# stm32070.net
KiCad netlist of a schematic drawn in Altium Designer
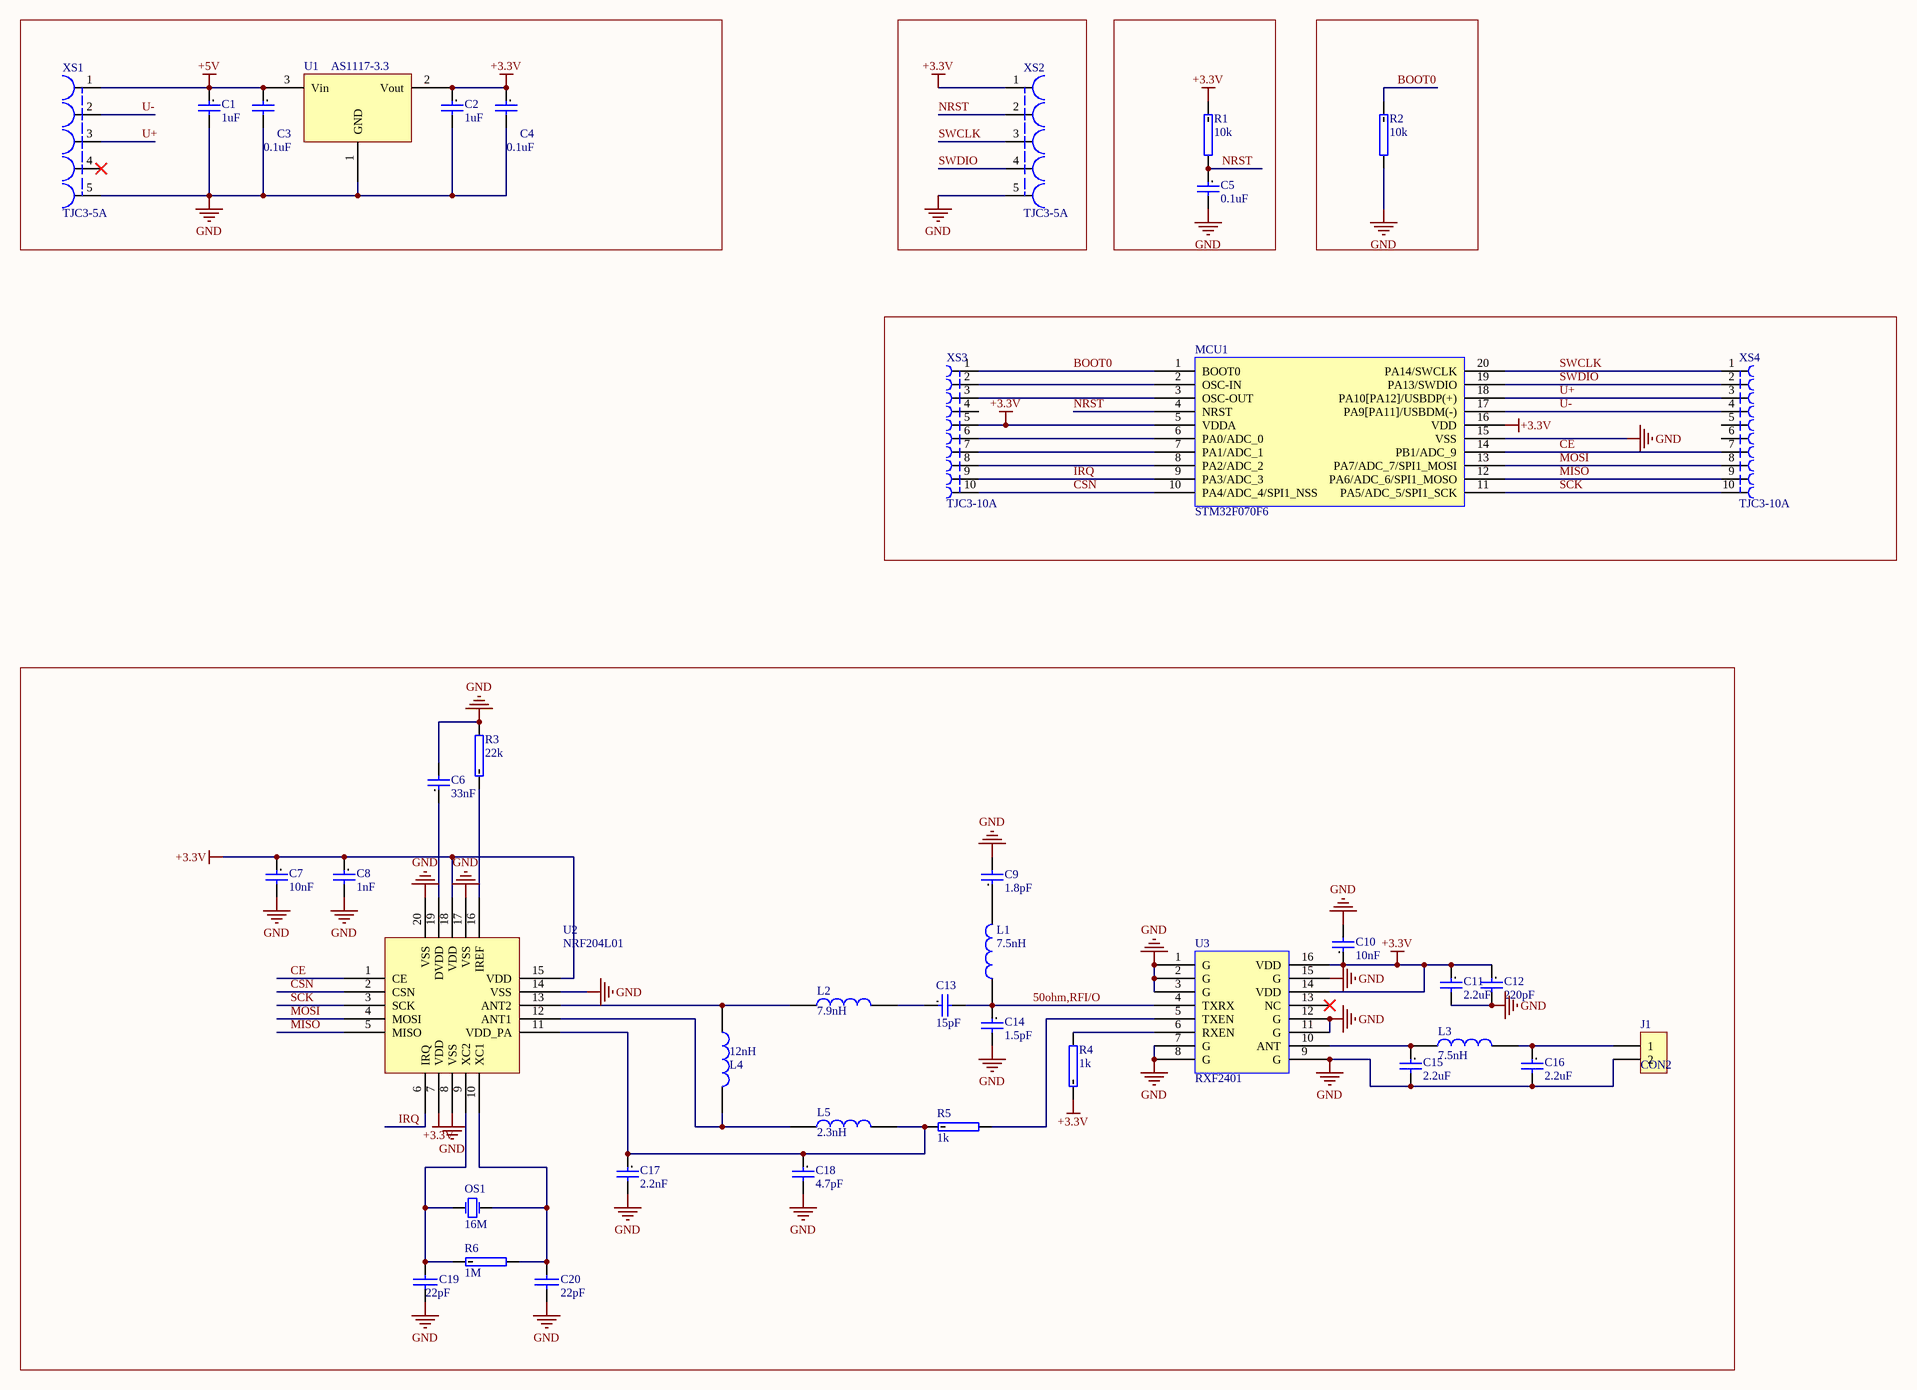
[diagram p0: stm32070.SchDoc]

(export (version "E")
  (design (tool "Eeschema 10.0.6"))
  (components
    (comp (ref "C1") (value "1uF") (footprint "0603C") (libsource (lib "JunraySCH") (part "CAP")))
    (comp (ref "C2") (value "1uF") (footprint "0603C") (libsource (lib "JunraySCH") (part "CAP")))
    (comp (ref "C3") (value "0.1uF") (footprint "0603C") (libsource (lib "JunraySCH") (part "CAP")))
    (comp (ref "C4") (value "0.1uF") (footprint "0603C") (libsource (lib "JunraySCH") (part "CAP")))
    (comp (ref "C5") (value "0.1uF") (footprint "0603C") (libsource (lib "JunraySCH") (part "CAP")))
    (comp (ref "C6") (value "33nF") (footprint "0603C") (libsource (lib "JunraySCH") (part "CAP")))
    (comp (ref "C7") (value "10nF") (footprint "0603C") (libsource (lib "JunraySCH") (part "CAP")))
    (comp (ref "C8") (value "1nF") (footprint "0603C") (libsource (lib "JunraySCH") (part "CAP")))
    (comp (ref "C9") (value "1.8pF") (footprint "0603C") (libsource (lib "JunraySCH") (part "CAP")))
    (comp (ref "C10") (value "10nF") (footprint "0603C") (libsource (lib "JunraySCH") (part "CAP")))
    (comp (ref "C11") (value "2.2uF") (footprint "0603C") (libsource (lib "JunraySCH") (part "CAP")))
    (comp (ref "C12") (value "220pF") (footprint "0603C") (libsource (lib "JunraySCH") (part "CAP")))
    (comp (ref "C13") (value "15pF") (footprint "0603C") (libsource (lib "JunraySCH") (part "CAP")))
    (comp (ref "C14") (value "1.5pF") (footprint "0603C") (libsource (lib "JunraySCH") (part "CAP")))
    (comp (ref "C15") (value "2.2uF") (footprint "0603C") (libsource (lib "JunraySCH") (part "CAP")))
    (comp (ref "C16") (value "2.2uF") (footprint "0603C") (libsource (lib "JunraySCH") (part "CAP")))
    (comp (ref "C17") (value "2.2nF") (footprint "0603C") (libsource (lib "JunraySCH") (part "CAP")))
    (comp (ref "C18") (value "4.7pF") (footprint "0603C") (libsource (lib "JunraySCH") (part "CAP")))
    (comp (ref "C19")
      (value "22pF")
      (footprint "0603C")
      (description "Capacitor")
      (libsource (lib "*") (part "CAP"))
    )
    (comp (ref "C20")
      (value "22pF")
      (footprint "0603C")
      (description "Capacitor")
      (libsource (lib "*") (part "CAP"))
    )
    (comp (ref "J1")
      (value "CON2")
      (footprint "同轴连接器")
      (description "Connector")
      (libsource (lib "*") (part "CON2"))
    )
    (comp (ref "L1") (value "7.5nH") (footprint "0603R") (libsource (lib "*") (part "INDUCTOR")))
    (comp (ref "L2") (value "7.9nH") (footprint "0603R") (libsource (lib "*") (part "INDUCTOR")))
    (comp (ref "L3") (value "7.5nH") (footprint "0603R") (libsource (lib "*") (part "INDUCTOR")))
    (comp (ref "L4") (value "12nH") (footprint "0603R") (libsource (lib "*") (part "INDUCTOR")))
    (comp (ref "L5") (value "2.3nH") (footprint "0603R") (libsource (lib "*") (part "INDUCTOR")))
    (comp (ref "MCU1")
      (value "STM32F070F6")
      (footprint "TSSOP20")
      (libsource (lib "JunraySCH") (part "STM32F070F6"))
    )
    (comp (ref "OS1") (value "16M") (footprint "晶振-5032-4P") (libsource (lib "JunraySCH") (part "XTAL")))
    (comp (ref "R1") (value "10k") (footprint "0603R") (libsource (lib "JunraySCH") (part "RSE1")))
    (comp (ref "R2") (value "10k") (footprint "0603R") (libsource (lib "JunraySCH") (part "RSE1")))
    (comp (ref "R3") (value "22k") (footprint "0603R") (libsource (lib "JunraySCH") (part "RSE1")))
    (comp (ref "R4") (value "1k") (footprint "0603R") (libsource (lib "JunraySCH") (part "RSE1")))
    (comp (ref "R5") (value "1k") (footprint "0603R") (libsource (lib "JunraySCH") (part "RSE1")))
    (comp (ref "R6") (value "1M") (footprint "0603R") (libsource (lib "JunraySCH") (part "RSE1")))
    (comp (ref "U1")
      (value "AS1117-3.3")
      (footprint "SOT-89")
      (libsource (lib "JunraySCH") (part "AS1117-3.3"))
    )
    (comp (ref "U2") (value "NRF204L01") (footprint "QFN20") (libsource (lib "JunraySCH") (part "NRF204L01")))
    (comp (ref "U3") (value "RXF2401") (footprint "QFN16") (libsource (lib "JunraySCH") (part "RXF2401C")))
    (comp (ref "XS1") (value "TJC3-5A") (footprint "MicorUSB 手机插座") (libsource (lib "") (part "TJC3-5A_1")))
    (comp (ref "XS2") (value "TJC3-5A") (footprint "SIP-5") (libsource (lib "JunraySCH") (part "TJC3-5A")))
    (comp (ref "XS3") (value "TJC3-10A") (footprint "SIP-10") (libsource (lib "JunraySCH") (part "TJC3-10A")))
    (comp (ref "XS4") (value "TJC3-10A") (footprint "SIP-10") (libsource (lib "") (part "TJC3-10A_1")))
  )
  (nets
    (net (code "1") (name "+3.3V") (class "Default")
      (node (ref "C10") (pin "1") (pinfunction "1_1") (pintype "passive"))
      (node (ref "C11") (pin "1") (pinfunction "1_1") (pintype "passive"))
      (node (ref "C12") (pin "1") (pinfunction "1_1") (pintype "passive"))
      (node (ref "C2") (pin "1") (pinfunction "1_1") (pintype "passive"))
      (node (ref "C4") (pin "1") (pinfunction "1_1") (pintype "passive"))
      (node (ref "C7") (pin "1") (pinfunction "1_1") (pintype "passive"))
      (node (ref "C8") (pin "1") (pinfunction "1_1") (pintype "passive"))
      (node (ref "MCU1") (pin "16") (pinfunction "VDD_16") (pintype "passive"))
      (node (ref "MCU1") (pin "5") (pinfunction "VDDA_5") (pintype "passive"))
      (node (ref "R1") (pin "1") (pinfunction "1_1") (pintype "passive"))
      (node (ref "R4") (pin "1") (pinfunction "1_1") (pintype "passive"))
      (node (ref "U1") (pin "2") (pinfunction "Vout_2") (pintype "passive"))
      (node (ref "U2") (pin "15") (pinfunction "VDD_15") (pintype "passive"))
      (node (ref "U2") (pin "18") (pinfunction "VDD_18") (pintype "passive"))
      (node (ref "U2") (pin "7") (pinfunction "VDD_7") (pintype "passive"))
      (node (ref "U3") (pin "14") (pinfunction "VDD_14") (pintype "passive"))
      (node (ref "U3") (pin "16") (pinfunction "VDD_16") (pintype "passive"))
      (node (ref "XS2") (pin "1") (pintype "passive"))
      (node (ref "XS3") (pin "5") (pintype "passive"))
    )
    (net (code "2") (name "+5V") (class "Default")
      (node (ref "C1") (pin "1") (pinfunction "1_1") (pintype "passive"))
      (node (ref "C3") (pin "1") (pinfunction "1_1") (pintype "passive"))
      (node (ref "U1") (pin "3") (pinfunction "Vin_3") (pintype "passive"))
      (node (ref "XS1") (pin "1") (pintype "passive"))
    )
    (net (code "3") (name "/50ohm,RFI{slash}O") (class "Default")
      (node (ref "C13") (pin "2") (pinfunction "2_2") (pintype "passive"))
      (node (ref "C14") (pin "1") (pinfunction "1_1") (pintype "passive"))
      (node (ref "L1") (pin "1") (pinfunction "1_1") (pintype "passive"))
      (node (ref "U3") (pin "4") (pinfunction "TXRX_4") (pintype "passive"))
    )
    (net (code "4") (name "/BOOT0") (class "Default")
      (node (ref "MCU1") (pin "1") (pinfunction "BOOT0_1") (pintype "passive"))
      (node (ref "R2") (pin "1") (pinfunction "1_1") (pintype "passive"))
      (node (ref "XS3") (pin "1") (pintype "passive"))
    )
    (net (code "5") (name "/CE") (class "Default")
      (node (ref "MCU1") (pin "14") (pinfunction "PB1/ADC_9_14") (pintype "passive"))
      (node (ref "U2") (pin "1") (pinfunction "CE_1") (pintype "passive"))
      (node (ref "XS4") (pin "7") (pintype "passive"))
    )
    (net (code "6") (name "/CSN") (class "Default")
      (node (ref "MCU1") (pin "10") (pinfunction "PA4/ADC_4/SPI1_NSS_10") (pintype "passive"))
      (node (ref "U2") (pin "2") (pinfunction "CSN_2") (pintype "passive"))
      (node (ref "XS3") (pin "10") (pintype "passive"))
    )
    (net (code "7") (name "/IRQ") (class "Default")
      (node (ref "MCU1") (pin "9") (pinfunction "PA3/ADC_3_9") (pintype "passive"))
      (node (ref "U2") (pin "6") (pinfunction "IRQ_6") (pintype "passive"))
      (node (ref "XS3") (pin "9") (pintype "passive"))
    )
    (net (code "8") (name "/MISO") (class "Default")
      (node (ref "MCU1") (pin "12") (pinfunction "PA6/ADC_6/SPI1_MOSO_12") (pintype "passive"))
      (node (ref "U2") (pin "5") (pinfunction "MISO_5") (pintype "passive"))
      (node (ref "XS4") (pin "9") (pintype "passive"))
    )
    (net (code "9") (name "/MOSI") (class "Default")
      (node (ref "MCU1") (pin "13") (pinfunction "PA7/ADC_7/SPI1_MOSI_13") (pintype "passive"))
      (node (ref "U2") (pin "4") (pinfunction "MOSI_4") (pintype "passive"))
      (node (ref "XS4") (pin "8") (pintype "passive"))
    )
    (net (code "10") (name "/NRST") (class "Default")
      (node (ref "C5") (pin "1") (pinfunction "1_1") (pintype "passive"))
      (node (ref "MCU1") (pin "4") (pinfunction "NRST_4") (pintype "passive"))
      (node (ref "R1") (pin "2") (pinfunction "2_2") (pintype "passive"))
      (node (ref "XS2") (pin "2") (pintype "passive"))
    )
    (net (code "11") (name "/SCK") (class "Default")
      (node (ref "MCU1") (pin "11") (pinfunction "PA5/ADC_5/SPI1_SCK_11") (pintype "passive"))
      (node (ref "U2") (pin "3") (pinfunction "SCK_3") (pintype "passive"))
      (node (ref "XS4") (pin "10") (pintype "passive"))
    )
    (net (code "12") (name "/SWCLK") (class "Default")
      (node (ref "MCU1") (pin "20") (pinfunction "PA14/SWCLK_20") (pintype "passive"))
      (node (ref "XS2") (pin "3") (pintype "passive"))
      (node (ref "XS4") (pin "1") (pintype "passive"))
    )
    (net (code "13") (name "/SWDIO") (class "Default")
      (node (ref "MCU1") (pin "19") (pinfunction "PA13/SWDIO_19") (pintype "passive"))
      (node (ref "XS2") (pin "4") (pintype "passive"))
      (node (ref "XS4") (pin "2") (pintype "passive"))
    )
    (net (code "14") (name "/U+") (class "Default")
      (node (ref "MCU1") (pin "18") (pinfunction "PA10[PA12]/USBDP(+)_18") (pintype "passive"))
      (node (ref "XS1") (pin "3") (pintype "passive"))
      (node (ref "XS4") (pin "3") (pintype "passive"))
    )
    (net (code "15") (name "/U-") (class "Default")
      (node (ref "MCU1") (pin "17") (pinfunction "PA9[PA11]/USBDM(-)_17") (pintype "passive"))
      (node (ref "XS1") (pin "2") (pintype "passive"))
      (node (ref "XS4") (pin "4") (pintype "passive"))
    )
    (net (code "16") (name "GND") (class "Default")
      (node (ref "C1") (pin "2") (pinfunction "2_2") (pintype "passive"))
      (node (ref "C10") (pin "2") (pinfunction "2_2") (pintype "passive"))
      (node (ref "C11") (pin "2") (pinfunction "2_2") (pintype "passive"))
      (node (ref "C12") (pin "2") (pinfunction "2_2") (pintype "passive"))
      (node (ref "C14") (pin "2") (pinfunction "2_2") (pintype "passive"))
      (node (ref "C15") (pin "2") (pinfunction "2_2") (pintype "passive"))
      (node (ref "C16") (pin "2") (pinfunction "2_2") (pintype "passive"))
      (node (ref "C17") (pin "2") (pinfunction "2_2") (pintype "passive"))
      (node (ref "C18") (pin "2") (pinfunction "2_2") (pintype "passive"))
      (node (ref "C19") (pin "2") (pinfunction "2_2") (pintype "passive"))
      (node (ref "C2") (pin "2") (pinfunction "2_2") (pintype "passive"))
      (node (ref "C20") (pin "2") (pinfunction "2_2") (pintype "passive"))
      (node (ref "C3") (pin "2") (pinfunction "2_2") (pintype "passive"))
      (node (ref "C4") (pin "2") (pinfunction "2_2") (pintype "passive"))
      (node (ref "C5") (pin "2") (pinfunction "2_2") (pintype "passive"))
      (node (ref "C6") (pin "2") (pinfunction "2_2") (pintype "passive"))
      (node (ref "C7") (pin "2") (pinfunction "2_2") (pintype "passive"))
      (node (ref "C8") (pin "2") (pinfunction "2_2") (pintype "passive"))
      (node (ref "C9") (pin "2") (pinfunction "2_2") (pintype "passive"))
      (node (ref "J1") (pin "2") (pinfunction "2_2") (pintype "passive"))
      (node (ref "MCU1") (pin "15") (pinfunction "VSS_15") (pintype "passive"))
      (node (ref "R2") (pin "2") (pinfunction "2_2") (pintype "passive"))
      (node (ref "R3") (pin "2") (pinfunction "2_2") (pintype "passive"))
      (node (ref "U1") (pin "1") (pinfunction "GND_1") (pintype "passive"))
      (node (ref "U2") (pin "14") (pinfunction "VSS_14") (pintype "passive"))
      (node (ref "U2") (pin "17") (pinfunction "VSS_17") (pintype "passive"))
      (node (ref "U2") (pin "20") (pinfunction "VSS_20") (pintype "passive"))
      (node (ref "U2") (pin "8") (pinfunction "VSS_8") (pintype "passive"))
      (node (ref "U3") (pin "1") (pinfunction "G_1") (pintype "passive"))
      (node (ref "U3") (pin "11") (pinfunction "G_11") (pintype "passive"))
      (node (ref "U3") (pin "12") (pinfunction "G_12") (pintype "passive"))
      (node (ref "U3") (pin "15") (pinfunction "G_15") (pintype "passive"))
      (node (ref "U3") (pin "2") (pinfunction "G_2") (pintype "passive"))
      (node (ref "U3") (pin "3") (pinfunction "G_3") (pintype "passive"))
      (node (ref "U3") (pin "7") (pinfunction "G_7") (pintype "passive"))
      (node (ref "U3") (pin "8") (pinfunction "G_8") (pintype "passive"))
      (node (ref "U3") (pin "9") (pinfunction "G_9") (pintype "passive"))
      (node (ref "XS1") (pin "5") (pintype "passive"))
      (node (ref "XS2") (pin "5") (pintype "passive"))
    )
    (net (code "17") (name "Net-(C9-Pad1)") (class "Default")
      (node (ref "C9") (pin "1") (pinfunction "1_1") (pintype "passive"))
      (node (ref "L1") (pin "2") (pinfunction "2_2") (pintype "passive"))
    )
    (net (code "18") (name "Net-(C13-Pad1)") (class "Default")
      (node (ref "C13") (pin "1") (pinfunction "1_1") (pintype "passive"))
      (node (ref "L2") (pin "2") (pinfunction "2_2") (pintype "passive"))
    )
    (net (code "19") (name "Net-(C16-Pad1)") (class "Default")
      (node (ref "C16") (pin "1") (pinfunction "1_1") (pintype "passive"))
      (node (ref "J1") (pin "1") (pinfunction "1_1") (pintype "passive"))
      (node (ref "L3") (pin "2") (pinfunction "2_2") (pintype "passive"))
    )
    (net (code "20") (name "Net-(MCU1-OSC-IN)") (class "Default")
      (node (ref "MCU1") (pin "2") (pinfunction "OSC-IN_2") (pintype "passive"))
      (node (ref "XS3") (pin "2") (pintype "passive"))
    )
    (net (code "21") (name "Net-(MCU1-OSC-OUT)") (class "Default")
      (node (ref "MCU1") (pin "3") (pinfunction "OSC-OUT_3") (pintype "passive"))
      (node (ref "XS3") (pin "3") (pintype "passive"))
    )
    (net (code "22") (name "Net-(MCU1-PA0{slash}ADC_0)") (class "Default")
      (node (ref "MCU1") (pin "6") (pinfunction "PA0/ADC_0_6") (pintype "passive"))
      (node (ref "XS3") (pin "6") (pintype "passive"))
    )
    (net (code "23") (name "Net-(MCU1-PA1{slash}ADC_1)") (class "Default")
      (node (ref "MCU1") (pin "7") (pinfunction "PA1/ADC_1_7") (pintype "passive"))
      (node (ref "XS3") (pin "7") (pintype "passive"))
    )
    (net (code "24") (name "Net-(MCU1-PA2{slash}ADC_2)") (class "Default")
      (node (ref "MCU1") (pin "8") (pinfunction "PA2/ADC_2_8") (pintype "passive"))
      (node (ref "XS3") (pin "8") (pintype "passive"))
    )
    (net (code "25") (name "Net-(OS1-OSC1)") (class "Default")
      (node (ref "C19") (pin "1") (pinfunction "1_1") (pintype "passive"))
      (node (ref "OS1") (pin "1") (pinfunction "OSC1_1") (pintype "passive"))
      (node (ref "R6") (pin "1") (pinfunction "1_1") (pintype "passive"))
      (node (ref "U2") (pin "9") (pinfunction "XC2_9") (pintype "passive"))
    )
    (net (code "26") (name "Net-(OS1-OSC2)") (class "Default")
      (node (ref "C20") (pin "1") (pinfunction "1_1") (pintype "passive"))
      (node (ref "OS1") (pin "2") (pinfunction "OSC2_2") (pintype "passive"))
      (node (ref "R6") (pin "2") (pinfunction "2_2") (pintype "passive"))
      (node (ref "U2") (pin "10") (pinfunction "XC1_10") (pintype "passive"))
    )
    (net (code "27") (name "Net-(U2-ANT1)") (class "Default")
      (node (ref "L4") (pin "2") (pinfunction "2_2") (pintype "passive"))
      (node (ref "L5") (pin "1") (pinfunction "1_1") (pintype "passive"))
      (node (ref "U2") (pin "12") (pinfunction "ANT1_12") (pintype "passive"))
    )
    (net (code "28") (name "Net-(U2-ANT2)") (class "Default")
      (node (ref "L2") (pin "1") (pinfunction "1_1") (pintype "passive"))
      (node (ref "L4") (pin "1") (pinfunction "1_1") (pintype "passive"))
      (node (ref "U2") (pin "13") (pinfunction "ANT2_13") (pintype "passive"))
    )
    (net (code "29") (name "Net-(U2-DVDD)") (class "Default")
      (node (ref "C6") (pin "1") (pinfunction "1_1") (pintype "passive"))
      (node (ref "U2") (pin "19") (pinfunction "DVDD_19") (pintype "passive"))
    )
    (net (code "30") (name "Net-(U2-IREF)") (class "Default")
      (node (ref "R3") (pin "1") (pinfunction "1_1") (pintype "passive"))
      (node (ref "U2") (pin "16") (pinfunction "IREF_16") (pintype "passive"))
    )
    (net (code "31") (name "Net-(U2-VDD_PA)") (class "Default")
      (node (ref "C17") (pin "1") (pinfunction "1_1") (pintype "passive"))
      (node (ref "C18") (pin "1") (pinfunction "1_1") (pintype "passive"))
      (node (ref "L5") (pin "2") (pinfunction "2_2") (pintype "passive"))
      (node (ref "R5") (pin "1") (pinfunction "1_1") (pintype "passive"))
      (node (ref "U2") (pin "11") (pinfunction "VDD_PA_11") (pintype "passive"))
    )
    (net (code "32") (name "Net-(U3-ANT)") (class "Default")
      (node (ref "C15") (pin "1") (pinfunction "1_1") (pintype "passive"))
      (node (ref "L3") (pin "1") (pinfunction "1_1") (pintype "passive"))
      (node (ref "U3") (pin "10") (pinfunction "ANT_10") (pintype "passive"))
    )
    (net (code "33") (name "Net-(U3-RXEN)") (class "Default")
      (node (ref "R4") (pin "2") (pinfunction "2_2") (pintype "passive"))
      (node (ref "U3") (pin "6") (pinfunction "RXEN_6") (pintype "passive"))
    )
    (net (code "34") (name "Net-(U3-TXEN)") (class "Default")
      (node (ref "R5") (pin "2") (pinfunction "2_2") (pintype "passive"))
      (node (ref "U3") (pin "5") (pinfunction "TXEN_5") (pintype "passive"))
    )
    (net (code "35") (name "unconnected-(U3-NC-Pad13)") (class "Default")
      (node (ref "U3") (pin "13") (pinfunction "NC_13") (pintype "passive+no_connect"))
    )
    (net (code "36") (name "unconnected-(XS1-Pad4)") (class "Default")
      (node (ref "XS1") (pin "4") (pintype "passive+no_connect"))
    )
    (net (code "37") (name "unconnected-(XS3-Pad4)") (class "Default")
      (node (ref "XS3") (pin "4") (pintype "passive"))
    )
    (net (code "38") (name "unconnected-(XS4-Pad5)") (class "Default")
      (node (ref "XS4") (pin "5") (pintype "passive"))
    )
    (net (code "39") (name "unconnected-(XS4-Pad6)") (class "Default")
      (node (ref "XS4") (pin "6") (pintype "passive"))
    )
  )
)
